# LOGIC.net
KiCad netlist of a schematic drawn in Altium Designer
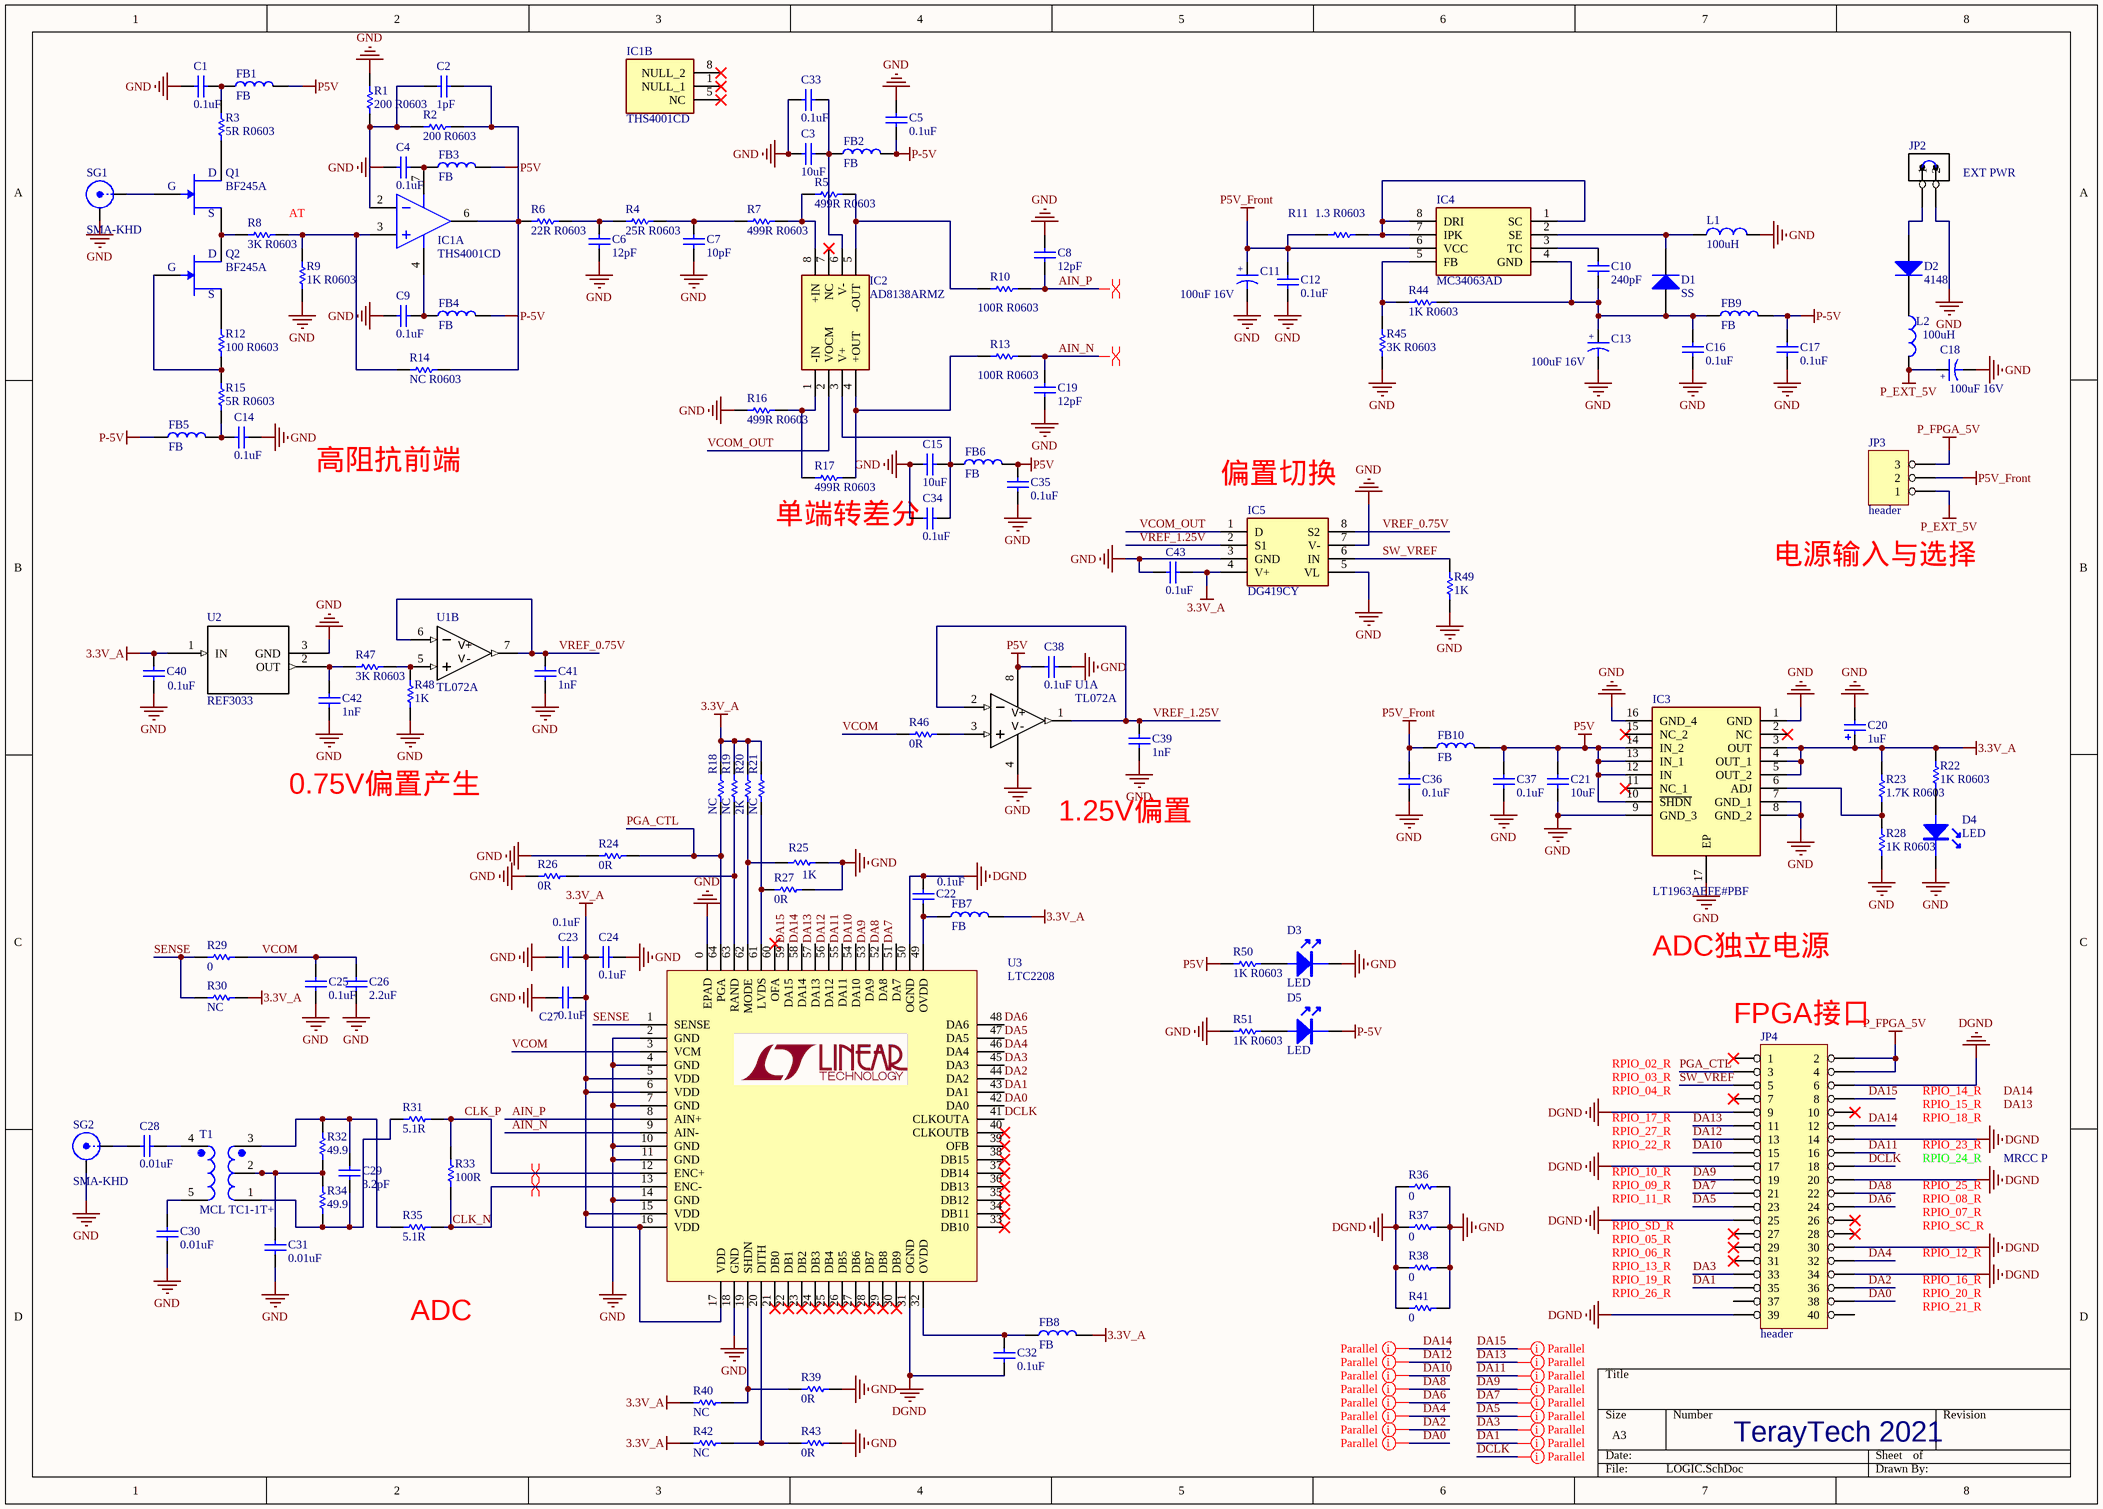
[diagram p0: LOGIC.SchDoc]

(export (version "E")
  (design (tool "Eeschema 10.0.6"))
  (components
    (comp (ref "C1")
      (value "0.1uF")
      (footprint "0603_C")
      (description "Capacitor")
      (fields (field (name "PUBLISHER") "Altium Limited"))
      (libsource (lib "My Footprint") (part "CAP"))
    )
    (comp (ref "C2")
      (value "1pF")
      (footprint "0603_C")
      (description "Capacitor")
      (fields (field (name "PUBLISHER") "Altium Limited"))
      (libsource (lib "My Footprint") (part "CAP"))
    )
    (comp (ref "C3")
      (value "10uF")
      (footprint "0805_c")
      (description "Capacitor")
      (fields (field (name "PUBLISHER") "Altium Limited"))
      (libsource (lib "My Footprint") (part "CAP"))
    )
    (comp (ref "C4")
      (value "0.1uF")
      (footprint "0603_C")
      (description "Capacitor")
      (fields (field (name "PUBLISHER") "Altium Limited"))
      (libsource (lib "My Footprint") (part "CAP"))
    )
    (comp (ref "C5")
      (value "0.1uF")
      (footprint "0603_C")
      (description "Capacitor")
      (fields (field (name "PUBLISHER") "Altium Limited"))
      (libsource (lib "My Footprint") (part "CAP"))
    )
    (comp (ref "C6")
      (value "12pF")
      (footprint "0603_C")
      (description "Capacitor")
      (fields (field (name "PUBLISHER") "Altium Limited"))
      (libsource (lib "My Footprint") (part "CAP"))
    )
    (comp (ref "C7")
      (value "10pF")
      (footprint "0603_C")
      (description "Capacitor")
      (fields (field (name "PUBLISHER") "Altium Limited"))
      (libsource (lib "My Footprint") (part "CAP"))
    )
    (comp (ref "C8")
      (value "12pF")
      (footprint "0603_C")
      (description "Capacitor")
      (fields (field (name "PUBLISHER") "Altium Limited"))
      (libsource (lib "My Footprint") (part "CAP"))
    )
    (comp (ref "C9")
      (value "0.1uF")
      (footprint "0603_C")
      (description "Capacitor")
      (fields (field (name "PUBLISHER") "Altium Limited"))
      (libsource (lib "My Footprint") (part "CAP"))
    )
    (comp (ref "C10")
      (value "240pF")
      (footprint "0603_C")
      (description "Capacitor")
      (fields (field (name "PUBLISHER") "Altium Limited"))
      (libsource (lib "My Footprint") (part "CAP"))
    )
    (comp (ref "C11")
      (value "100uF 16V")
      (footprint "CAP_1000x2000")
      (libsource (lib "My Footprint") (part "CAP1"))
    )
    (comp (ref "C12")
      (value "0.1uF")
      (footprint "0603_C")
      (description "Capacitor")
      (fields (field (name "PUBLISHER") "Altium Limited"))
      (libsource (lib "My Footprint") (part "CAP"))
    )
    (comp (ref "C13")
      (value "100uF 16V")
      (footprint "CAP_1000x2000")
      (libsource (lib "My Footprint") (part "CAP1"))
    )
    (comp (ref "C14")
      (value "0.1uF")
      (footprint "0603_C")
      (description "Capacitor")
      (fields (field (name "PUBLISHER") "Altium Limited"))
      (libsource (lib "My Footprint") (part "CAP"))
    )
    (comp (ref "C15")
      (value "10uF")
      (footprint "0805_c")
      (description "Capacitor")
      (fields (field (name "PUBLISHER") "Altium Limited"))
      (libsource (lib "My Footprint") (part "CAP"))
    )
    (comp (ref "C16")
      (value "0.1uF")
      (footprint "0805_c")
      (description "Capacitor")
      (fields (field (name "PUBLISHER") "Altium Limited"))
      (libsource (lib "My Footprint") (part "CAP"))
    )
    (comp (ref "C17")
      (value "0.1uF")
      (footprint "0805_c")
      (description "Capacitor")
      (fields (field (name "PUBLISHER") "Altium Limited"))
      (libsource (lib "My Footprint") (part "CAP"))
    )
    (comp (ref "C18")
      (value "100uF 16V")
      (footprint "CAP_1000x2000")
      (libsource (lib "My Footprint") (part "CAP1"))
    )
    (comp (ref "C19")
      (value "12pF")
      (footprint "0603_C")
      (description "Capacitor")
      (fields (field (name "PUBLISHER") "Altium Limited"))
      (libsource (lib "My Footprint") (part "CAP"))
    )
    (comp (ref "C20")
      (value "1uF")
      (footprint "CAPC3528B")
      (description "Capacitor")
      (fields (field (name "PUBLISHER") "Altium Limited"))
      (libsource (lib "My Footprint") (part "CAP_tan"))
    )
    (comp (ref "C21")
      (value "10uF")
      (footprint "0805_c")
      (description "Capacitor")
      (fields (field (name "PUBLISHER") "Altium Limited"))
      (libsource (lib "My Footprint") (part "CAP"))
    )
    (comp (ref "C22")
      (value "0.1uF")
      (footprint "0603_C")
      (description "Capacitor")
      (fields (field (name "PUBLISHER") "Altium Limited"))
      (libsource (lib "My Footprint") (part "CAP"))
    )
    (comp (ref "C23")
      (value "0.1uF")
      (footprint "0603_C")
      (description "Capacitor")
      (fields (field (name "PUBLISHER") "Altium Limited"))
      (libsource (lib "My Footprint") (part "CAP"))
    )
    (comp (ref "C24")
      (value "0.1uF")
      (footprint "0603_C")
      (description "Capacitor")
      (fields (field (name "PUBLISHER") "Altium Limited"))
      (libsource (lib "My Footprint") (part "CAP"))
    )
    (comp (ref "C25")
      (value "0.1uF")
      (footprint "0603_C")
      (description "Capacitor")
      (fields (field (name "PUBLISHER") "Altium Limited"))
      (libsource (lib "My Footprint") (part "CAP"))
    )
    (comp (ref "C26")
      (value "2.2uF")
      (footprint "0603_C")
      (description "Capacitor")
      (fields (field (name "PUBLISHER") "Altium Limited"))
      (libsource (lib "My Footprint") (part "CAP"))
    )
    (comp (ref "C27")
      (value "0.1uF")
      (footprint "0603_C")
      (description "Capacitor")
      (fields (field (name "PUBLISHER") "Altium Limited"))
      (libsource (lib "My Footprint") (part "CAP"))
    )
    (comp (ref "C28")
      (value "0.01uF")
      (footprint "0603_C")
      (description "Capacitor")
      (fields (field (name "PUBLISHER") "Altium Limited"))
      (libsource (lib "My Footprint") (part "CAP"))
    )
    (comp (ref "C29")
      (value "8.2pF")
      (footprint "0603_C")
      (description "Capacitor")
      (fields (field (name "PUBLISHER") "Altium Limited"))
      (libsource (lib "My Footprint") (part "CAP"))
    )
    (comp (ref "C30")
      (value "0.01uF")
      (footprint "0603_C")
      (description "Capacitor")
      (fields (field (name "PUBLISHER") "Altium Limited"))
      (libsource (lib "My Footprint") (part "CAP"))
    )
    (comp (ref "C31")
      (value "0.01uF")
      (footprint "0603_C")
      (description "Capacitor")
      (fields (field (name "PUBLISHER") "Altium Limited"))
      (libsource (lib "My Footprint") (part "CAP"))
    )
    (comp (ref "C32")
      (value "0.1uF")
      (footprint "0603_C")
      (description "Capacitor")
      (fields (field (name "PUBLISHER") "Altium Limited"))
      (libsource (lib "My Footprint") (part "CAP"))
    )
    (comp (ref "C33")
      (value "0.1uF")
      (footprint "0603_C")
      (description "Capacitor")
      (fields (field (name "PUBLISHER") "Altium Limited"))
      (libsource (lib "My Footprint") (part "CAP"))
    )
    (comp (ref "C34")
      (value "0.1uF")
      (footprint "0603_C")
      (description "Capacitor")
      (fields (field (name "PUBLISHER") "Altium Limited"))
      (libsource (lib "My Footprint") (part "CAP"))
    )
    (comp (ref "C35")
      (value "0.1uF")
      (footprint "0603_C")
      (description "Capacitor")
      (fields (field (name "PUBLISHER") "Altium Limited"))
      (libsource (lib "My Footprint") (part "CAP"))
    )
    (comp (ref "C36")
      (value "0.1uF")
      (footprint "0805_c")
      (description "Capacitor")
      (fields (field (name "PUBLISHER") "Altium Limited"))
      (libsource (lib "My Footprint") (part "CAP"))
    )
    (comp (ref "C37")
      (value "0.1uF")
      (footprint "0805_c")
      (description "Capacitor")
      (fields (field (name "PUBLISHER") "Altium Limited"))
      (libsource (lib "My Footprint") (part "CAP"))
    )
    (comp (ref "C38")
      (value "0.1uF")
      (footprint "0603_C")
      (description "Capacitor")
      (fields (field (name "PUBLISHER") "Altium Limited"))
      (libsource (lib "My Footprint") (part "CAP"))
    )
    (comp (ref "C39")
      (value "1nF")
      (footprint "0603_C")
      (description "Capacitor")
      (fields (field (name "PUBLISHER") "Altium Limited"))
      (libsource (lib "My Footprint") (part "CAP"))
    )
    (comp (ref "C40")
      (value "0.1uF")
      (footprint "0603_C")
      (description "Capacitor")
      (fields (field (name "PUBLISHER") "Altium Limited"))
      (libsource (lib "My Footprint") (part "CAP"))
    )
    (comp (ref "C41")
      (value "1nF")
      (footprint "0603_C")
      (description "Capacitor")
      (fields (field (name "PUBLISHER") "Altium Limited"))
      (libsource (lib "My Footprint") (part "CAP"))
    )
    (comp (ref "C42")
      (value "1nF")
      (footprint "0603_C")
      (description "Capacitor")
      (fields (field (name "PUBLISHER") "Altium Limited"))
      (libsource (lib "My Footprint") (part "CAP"))
    )
    (comp (ref "C43")
      (value "0.1uF")
      (footprint "0603_C")
      (description "Capacitor")
      (fields (field (name "PUBLISHER") "Altium Limited"))
      (libsource (lib "My Footprint") (part "CAP"))
    )
    (comp (ref "D1") (value "SS") (footprint "DO-214AC(") (libsource (lib "My Footprint") (part "SS24")))
    (comp (ref "D2")
      (value "4148")
      (footprint "DO-214AC(")
      (description "High Conductance Fast Diode")
      (fields (field (name "PUBLISHER") "Altium Limited"))
      (libsource (lib "My Footprint") (part "1N4148"))
    )
    (comp (ref "D3")
      (value "LED")
      (footprint "0603_LED")
      (description "LED 发光二极管")
      (libsource (lib "My Footprint") (part "LED"))
    )
    (comp (ref "D4")
      (value "LED")
      (footprint "0603_LED")
      (description "LED 发光二极管")
      (libsource (lib "My Footprint") (part "LED"))
    )
    (comp (ref "D5")
      (value "LED")
      (footprint "0603_LED")
      (description "LED 发光二极管")
      (libsource (lib "My Footprint") (part "LED"))
    )
    (comp (ref "FB1")
      (value "FB")
      (footprint "FB0603")
      (description "磁珠")
      (libsource (lib "My Footprint") (part "FB"))
    )
    (comp (ref "FB2")
      (value "FB")
      (footprint "FB0603")
      (description "磁珠")
      (libsource (lib "My Footprint") (part "FB"))
    )
    (comp (ref "FB3")
      (value "FB")
      (footprint "FB0603")
      (description "磁珠")
      (libsource (lib "My Footprint") (part "FB"))
    )
    (comp (ref "FB4")
      (value "FB")
      (footprint "FB0603")
      (description "磁珠")
      (libsource (lib "My Footprint") (part "FB"))
    )
    (comp (ref "FB5")
      (value "FB")
      (footprint "FB0603")
      (description "磁珠")
      (libsource (lib "My Footprint") (part "FB"))
    )
    (comp (ref "FB6")
      (value "FB")
      (footprint "FB0603")
      (description "磁珠")
      (libsource (lib "My Footprint") (part "FB"))
    )
    (comp (ref "FB7")
      (value "FB")
      (footprint "FB0603")
      (description "磁珠")
      (libsource (lib "My Footprint") (part "FB"))
    )
    (comp (ref "FB8")
      (value "FB")
      (footprint "0603")
      (description "磁珠")
      (libsource (lib "My Footprint") (part "FB"))
    )
    (comp (ref "FB9")
      (value "FB")
      (footprint "0805")
      (description "磁珠")
      (libsource (lib "My Footprint") (part "FB"))
    )
    (comp (ref "FB10")
      (value "FB")
      (footprint "0805")
      (description "磁珠")
      (libsource (lib "My Footprint") (part "FB"))
    )
    (comp (ref "IC1")
      (value "THS4001CD")
      (footprint "SamacSys:SOIC127P600X175-8N")
      (description "Integrated Circuit")
      (fields (field (name "MOUSER PART NUMBER") "595-THS4001CD"))
      (libsource (lib "SamacSys") (part "THS4001CD"))
    )
    (comp (ref "IC2")
      (value "AD8138ARMZ")
      (footprint "SamacSys:SOP65P490X110-8N")
      (description "Integrated Circuit")
      (fields (field (name "MOUSER PART NUMBER") "584-AD8138ARMZ"))
      (libsource (lib "SamacSys") (part "AD8138ARMZ"))
    )
    (comp (ref "IC3")
      (value "LT1963AEFE#PBF")
      (footprint "SOP65P640X110-17N")
      (description "Integrated Circuit")
      (fields (field (name "MOUSER PART NUMBER") "584-LT1963AEFE#PBF"))
      (libsource (lib "SamacSys") (part "LT1963AEFE#PBF"))
    )
    (comp (ref "IC4")
      (value "MC34063AD")
      (footprint "SamacSys:SOIC127P600X175-8N")
      (description "Integrated Circuit")
      (fields (field (name "MOUSER PART NUMBER") "595-MC34063AD"))
      (libsource (lib "SamacSys") (part "MC34063AD"))
    )
    (comp (ref "IC5")
      (value "DG419CY")
      (footprint "SOIC-8")
      (description "Integrated Circuit")
      (libsource (lib "SamacSys") (part "DG419CY"))
    )
    (comp (ref "JP2")
      (value "EXT PWR")
      (footprint "CCM-5.08-2P")
      (libsource (lib "My Footprint") (part "HEADER 2"))
    )
    (comp (ref "JP3")
      (value "header")
      (footprint "header3")
      (libsource (lib "My Footprint") (part "HEADER 3"))
    )
    (comp (ref "JP4")
      (value "header")
      (footprint "header2X20")
      (libsource (lib "My Footprint") (part "HEADER 20X2"))
    )
    (comp (ref "L1") (value "100uH") (footprint "L 5x5") (libsource (lib "My Footprint") (part "Inductor")))
    (comp (ref "L2") (value "100uH") (footprint "1206") (libsource (lib "My Footprint") (part "Inductor")))
    (comp (ref "Q1")
      (value "BF245A")
      (footprint "SamacSys:TO127P419X482X1041-3P")
      (description "Transistor")
      (fields (field (name "MOUSER PART NUMBER") "863-BF245A"))
      (libsource (lib "SamacSys") (part "BF245A"))
    )
    (comp (ref "Q2")
      (value "BF245A")
      (footprint "SamacSys:TO127P419X482X1041-3P")
      (description "Transistor")
      (fields (field (name "MOUSER PART NUMBER") "863-BF245A"))
      (libsource (lib "SamacSys") (part "BF245A"))
    )
    (comp (ref "R1")
      (value "200 R0603")
      (footprint "0603_R")
      (description "Resistor")
      (fields (field (name "PUBLISHER") "Altium Limited"))
      (libsource (lib "My Footprint") (part "RES"))
    )
    (comp (ref "R2")
      (value "200 R0603")
      (footprint "0603_R")
      (description "Resistor")
      (fields (field (name "PUBLISHER") "Altium Limited"))
      (libsource (lib "My Footprint") (part "RES"))
    )
    (comp (ref "R3")
      (value "5R R0603")
      (footprint "0603_R")
      (description "Resistor")
      (fields (field (name "PUBLISHER") "Altium Limited"))
      (libsource (lib "My Footprint") (part "RES"))
    )
    (comp (ref "R4")
      (value "25R R0603")
      (footprint "0603_R")
      (description "Resistor")
      (fields (field (name "PUBLISHER") "Altium Limited"))
      (libsource (lib "My Footprint") (part "RES"))
    )
    (comp (ref "R5")
      (value "499R R0603")
      (footprint "0603_R")
      (description "Resistor")
      (fields (field (name "PUBLISHER") "Altium Limited"))
      (libsource (lib "My Footprint") (part "RES"))
    )
    (comp (ref "R6")
      (value "22R R0603")
      (footprint "0603_R")
      (description "Resistor")
      (fields (field (name "PUBLISHER") "Altium Limited"))
      (libsource (lib "My Footprint") (part "RES"))
    )
    (comp (ref "R7")
      (value "499R R0603")
      (footprint "0603_R")
      (description "Resistor")
      (fields (field (name "PUBLISHER") "Altium Limited"))
      (libsource (lib "My Footprint") (part "RES"))
    )
    (comp (ref "R8")
      (value "3K R0603")
      (footprint "0603_R")
      (description "Resistor")
      (fields (field (name "PUBLISHER") "Altium Limited"))
      (libsource (lib "My Footprint") (part "RES"))
    )
    (comp (ref "R9")
      (value "1K R0603")
      (footprint "0603_R")
      (description "Resistor")
      (fields (field (name "PUBLISHER") "Altium Limited"))
      (libsource (lib "My Footprint") (part "RES"))
    )
    (comp (ref "R10")
      (value "100R R0603")
      (footprint "0603_R")
      (description "Resistor")
      (fields (field (name "PUBLISHER") "Altium Limited"))
      (libsource (lib "My Footprint") (part "RES"))
    )
    (comp (ref "R11")
      (value "1.3 R0603")
      (footprint "0603_R")
      (description "Resistor")
      (fields (field (name "PUBLISHER") "Altium Limited"))
      (libsource (lib "My Footprint") (part "RES"))
    )
    (comp (ref "R12")
      (value "100 R0603")
      (footprint "0603_R")
      (description "Resistor")
      (fields (field (name "PUBLISHER") "Altium Limited"))
      (libsource (lib "My Footprint") (part "RES"))
    )
    (comp (ref "R13")
      (value "100R R0603")
      (footprint "0603_R")
      (description "Resistor")
      (fields (field (name "PUBLISHER") "Altium Limited"))
      (libsource (lib "My Footprint") (part "RES"))
    )
    (comp (ref "R14")
      (value "NC R0603")
      (footprint "0603_R")
      (description "Resistor")
      (fields (field (name "PUBLISHER") "Altium Limited"))
      (libsource (lib "My Footprint") (part "RES"))
    )
    (comp (ref "R15")
      (value "5R R0603")
      (footprint "0603_R")
      (description "Resistor")
      (fields (field (name "PUBLISHER") "Altium Limited"))
      (libsource (lib "My Footprint") (part "RES"))
    )
    (comp (ref "R16")
      (value "499R R0603")
      (footprint "0603_R")
      (description "Resistor")
      (fields (field (name "PUBLISHER") "Altium Limited"))
      (libsource (lib "My Footprint") (part "RES"))
    )
    (comp (ref "R17")
      (value "499R R0603")
      (footprint "0603_R")
      (description "Resistor")
      (fields (field (name "PUBLISHER") "Altium Limited"))
      (libsource (lib "My Footprint") (part "RES"))
    )
    (comp (ref "R18")
      (value "NC")
      (footprint "0603_R")
      (description "Resistor")
      (fields (field (name "PUBLISHER") "Altium Limited"))
      (libsource (lib "My Footprint") (part "RES0"))
    )
    (comp (ref "R19")
      (value "NC")
      (footprint "0603_R")
      (description "Resistor")
      (fields (field (name "PUBLISHER") "Altium Limited"))
      (libsource (lib "My Footprint") (part "RES0"))
    )
    (comp (ref "R20")
      (value "2K")
      (footprint "0603_R")
      (description "Resistor")
      (fields (field (name "PUBLISHER") "Altium Limited"))
      (libsource (lib "My Footprint") (part "RES0"))
    )
    (comp (ref "R21")
      (value "NC")
      (footprint "0603_R")
      (description "Resistor")
      (fields (field (name "PUBLISHER") "Altium Limited"))
      (libsource (lib "My Footprint") (part "RES0"))
    )
    (comp (ref "R22")
      (value "1K R0603")
      (footprint "0603_R")
      (description "Resistor")
      (fields (field (name "PUBLISHER") "Altium Limited"))
      (libsource (lib "My Footprint") (part "RES"))
    )
    (comp (ref "R23")
      (value "1.7K R0603")
      (footprint "0603_R")
      (description "Resistor")
      (fields (field (name "PUBLISHER") "Altium Limited"))
      (libsource (lib "My Footprint") (part "RES"))
    )
    (comp (ref "R24")
      (value "0R")
      (footprint "0603_R")
      (description "Resistor")
      (fields (field (name "PUBLISHER") "Altium Limited"))
      (libsource (lib "My Footprint") (part "RES0"))
    )
    (comp (ref "R25")
      (value "1K")
      (footprint "0603_R")
      (description "Resistor")
      (fields (field (name "PUBLISHER") "Altium Limited"))
      (libsource (lib "My Footprint") (part "RES0"))
    )
    (comp (ref "R26")
      (value "0R")
      (footprint "0603_R")
      (description "Resistor")
      (fields (field (name "PUBLISHER") "Altium Limited"))
      (libsource (lib "My Footprint") (part "RES0"))
    )
    (comp (ref "R27")
      (value "0R")
      (footprint "0603_R")
      (description "Resistor")
      (fields (field (name "PUBLISHER") "Altium Limited"))
      (libsource (lib "My Footprint") (part "RES0"))
    )
    (comp (ref "R28")
      (value "1K R0603")
      (footprint "0603_R")
      (description "Resistor")
      (fields (field (name "PUBLISHER") "Altium Limited"))
      (libsource (lib "My Footprint") (part "RES"))
    )
    (comp (ref "R29")
      (value "0")
      (footprint "0603_R")
      (description "Resistor")
      (fields (field (name "PUBLISHER") "Altium Limited"))
      (libsource (lib "My Footprint") (part "RES0"))
    )
    (comp (ref "R30")
      (value "NC")
      (footprint "0603_R")
      (description "Resistor")
      (fields (field (name "PUBLISHER") "Altium Limited"))
      (libsource (lib "My Footprint") (part "RES0"))
    )
    (comp (ref "R31")
      (value "5.1R")
      (footprint "0603_R")
      (description "Resistor")
      (fields (field (name "PUBLISHER") "Altium Limited"))
      (libsource (lib "My Footprint") (part "RES0"))
    )
    (comp (ref "R32")
      (value "49.9")
      (footprint "0603_R")
      (description "Resistor")
      (fields (field (name "PUBLISHER") "Altium Limited"))
      (libsource (lib "My Footprint") (part "RES0"))
    )
    (comp (ref "R33")
      (value "100R")
      (footprint "0603_R")
      (description "Resistor")
      (fields (field (name "PUBLISHER") "Altium Limited"))
      (libsource (lib "My Footprint") (part "RES0"))
    )
    (comp (ref "R34")
      (value "49.9")
      (footprint "0603_R")
      (description "Resistor")
      (fields (field (name "PUBLISHER") "Altium Limited"))
      (libsource (lib "My Footprint") (part "RES0"))
    )
    (comp (ref "R35")
      (value "5.1R")
      (footprint "0603_R")
      (description "Resistor")
      (fields (field (name "PUBLISHER") "Altium Limited"))
      (libsource (lib "My Footprint") (part "RES0"))
    )
    (comp (ref "R36")
      (value "0")
      (footprint "0603_R")
      (description "Resistor")
      (fields (field (name "PUBLISHER") "Altium Limited"))
      (libsource (lib "My Footprint") (part "RES0"))
    )
    (comp (ref "R37")
      (value "0")
      (footprint "0603_R")
      (description "Resistor")
      (fields (field (name "PUBLISHER") "Altium Limited"))
      (libsource (lib "My Footprint") (part "RES0"))
    )
    (comp (ref "R38")
      (value "0")
      (footprint "0603_R")
      (description "Resistor")
      (fields (field (name "PUBLISHER") "Altium Limited"))
      (libsource (lib "My Footprint") (part "RES0"))
    )
    (comp (ref "R39")
      (value "0R")
      (footprint "0603_R")
      (description "Resistor")
      (fields (field (name "PUBLISHER") "Altium Limited"))
      (libsource (lib "My Footprint") (part "RES0"))
    )
    (comp (ref "R40")
      (value "NC")
      (footprint "0603_R")
      (description "Resistor")
      (fields (field (name "PUBLISHER") "Altium Limited"))
      (libsource (lib "My Footprint") (part "RES0"))
    )
    (comp (ref "R41")
      (value "0")
      (footprint "0603_R")
      (description "Resistor")
      (fields (field (name "PUBLISHER") "Altium Limited"))
      (libsource (lib "My Footprint") (part "RES0"))
    )
    (comp (ref "R42")
      (value "NC")
      (footprint "0603_R")
      (description "Resistor")
      (fields (field (name "PUBLISHER") "Altium Limited"))
      (libsource (lib "My Footprint") (part "RES0"))
    )
    (comp (ref "R43")
      (value "0R")
      (footprint "0603_R")
      (description "Resistor")
      (fields (field (name "PUBLISHER") "Altium Limited"))
      (libsource (lib "My Footprint") (part "RES0"))
    )
    (comp (ref "R44")
      (value "1K R0603")
      (footprint "0603_R")
      (description "Resistor")
      (fields (field (name "PUBLISHER") "Altium Limited"))
      (libsource (lib "My Footprint") (part "RES"))
    )
    (comp (ref "R45")
      (value "3K R0603")
      (footprint "0603_R")
      (description "Resistor")
      (fields (field (name "PUBLISHER") "Altium Limited"))
      (libsource (lib "My Footprint") (part "RES"))
    )
    (comp (ref "R46")
      (value "0R")
      (footprint "0603_R")
      (description "Resistor")
      (fields (field (name "PUBLISHER") "Altium Limited"))
      (libsource (lib "My Footprint") (part "RES0"))
    )
    (comp (ref "R47")
      (value "3K R0603")
      (footprint "0603_R")
      (description "Resistor")
      (fields (field (name "PUBLISHER") "Altium Limited"))
      (libsource (lib "My Footprint") (part "RES"))
    )
    (comp (ref "R48")
      (value "1K")
      (footprint "0603_R")
      (description "Resistor")
      (fields (field (name "PUBLISHER") "Altium Limited"))
      (libsource (lib "My Footprint") (part "RES0"))
    )
    (comp (ref "R49")
      (value "1K")
      (footprint "0603_R")
      (description "Resistor")
      (fields (field (name "PUBLISHER") "Altium Limited"))
      (libsource (lib "My Footprint") (part "RES0"))
    )
    (comp (ref "R50")
      (value "1K R0603")
      (footprint "0603_R")
      (description "Resistor")
      (fields (field (name "PUBLISHER") "Altium Limited"))
      (libsource (lib "My Footprint") (part "RES"))
    )
    (comp (ref "R51")
      (value "1K R0603")
      (footprint "0603_R")
      (description "Resistor")
      (fields (field (name "PUBLISHER") "Altium Limited"))
      (libsource (lib "My Footprint") (part "RES"))
    )
    (comp (ref "SG1") (value "SMA-KHD") (footprint "SMA-2") (libsource (lib "") (part "SMA_KHD_1")))
    (comp (ref "SG2")
      (value "SMA-KHD")
      (footprint "SMA-H - duplicate")
      (libsource (lib "My Footprint") (part "SMA_KHD"))
    )
    (comp (ref "T1")
      (value "MCL TC1-1T+")
      (footprint "TC1-1T")
      (libsource (lib "My Footprint") (part "TC1-1T+"))
    )
    (comp (ref "U1")
      (value "TL072A")
      (footprint "SOIC-8")
      (description "Imported")
      (fields
        (field (name "MANUFACTURER") "Texas Instruments")
        (field (name "GENERIC_PART_NUMBER") "OPA2365")
      )
      (libsource (lib "My Footprint") (part "OPA2365"))
    )
    (comp (ref "U2")
      (value "REF3033")
      (footprint "DBZ3")
      (description "Imported")
      (fields
        (field (name "MANUFACTURER") "Texas Instruments")
        (field (name "MANUFACTURER_PART_NUMBER") "ref3033_dbz_3")
      )
      (libsource (lib "My Footprint") (part "REF3033_DBZ_3"))
    )
    (comp (ref "U3") (value "LTC2208") (footprint "QFN64") (libsource (lib "My Footprint") (part "LTC2208")))
  )
  (nets
    (net (code "1") (name "/AIN_N") (class "Default")
      (node (ref "C19") (pin "2") (pinfunction "2_2") (pintype "passive"))
      (node (ref "R13") (pin "2") (pinfunction "2_2") (pintype "passive"))
      (node (ref "U3") (pin "9") (pinfunction "AIN-_9") (pintype "passive"))
    )
    (net (code "2") (name "/AIN_P") (class "Default")
      (node (ref "C8") (pin "1") (pinfunction "1_1") (pintype "passive"))
      (node (ref "R10") (pin "2") (pinfunction "2_2") (pintype "passive"))
      (node (ref "U3") (pin "8") (pinfunction "AIN+_8") (pintype "passive"))
    )
    (net (code "3") (name "/CLK_N") (class "Default")
      (node (ref "R33") (pin "2") (pinfunction "2_2") (pintype "passive"))
      (node (ref "R35") (pin "2") (pinfunction "2_2") (pintype "passive"))
      (node (ref "U3") (pin "13") (pinfunction "ENC-_13") (pintype "passive"))
    )
    (net (code "4") (name "/CLK_P") (class "Default")
      (node (ref "R31") (pin "2") (pinfunction "2_2") (pintype "passive"))
      (node (ref "R33") (pin "1") (pinfunction "1_1") (pintype "passive"))
      (node (ref "U3") (pin "12") (pinfunction "ENC+_12") (pintype "passive"))
    )
    (net (code "5") (name "/DA0") (class "Default")
      (node (ref "JP4") (pin "38") (pinfunction "38_38") (pintype "passive"))
      (node (ref "U3") (pin "42") (pinfunction "DA0_42") (pintype "passive"))
    )
    (net (code "6") (name "/DA1") (class "Default")
      (node (ref "JP4") (pin "35") (pinfunction "35_35") (pintype "passive"))
      (node (ref "U3") (pin "43") (pinfunction "DA1_43") (pintype "passive"))
    )
    (net (code "7") (name "/DA2") (class "Default")
      (node (ref "JP4") (pin "36") (pinfunction "36_36") (pintype "passive"))
      (node (ref "U3") (pin "44") (pinfunction "DA2_44") (pintype "passive"))
    )
    (net (code "8") (name "/DA3") (class "Default")
      (node (ref "JP4") (pin "33") (pinfunction "33_33") (pintype "passive"))
      (node (ref "U3") (pin "45") (pinfunction "DA3_45") (pintype "passive"))
    )
    (net (code "9") (name "/DA4") (class "Default")
      (node (ref "JP4") (pin "32") (pinfunction "32_32") (pintype "passive"))
      (node (ref "U3") (pin "46") (pinfunction "DA4_46") (pintype "passive"))
    )
    (net (code "10") (name "/DA5") (class "Default")
      (node (ref "JP4") (pin "23") (pinfunction "23_23") (pintype "passive"))
      (node (ref "U3") (pin "47") (pinfunction "DA5_47") (pintype "passive"))
    )
    (net (code "11") (name "/DA6") (class "Default")
      (node (ref "JP4") (pin "24") (pinfunction "24_24") (pintype "passive"))
      (node (ref "U3") (pin "48") (pinfunction "DA6_48") (pintype "passive"))
    )
    (net (code "12") (name "/DA7") (class "Default")
      (node (ref "JP4") (pin "21") (pinfunction "21_21") (pintype "passive"))
      (node (ref "U3") (pin "51") (pinfunction "DA7_51") (pintype "passive"))
    )
    (net (code "13") (name "/DA8") (class "Default")
      (node (ref "JP4") (pin "22") (pinfunction "22_22") (pintype "passive"))
      (node (ref "U3") (pin "52") (pinfunction "DA8_52") (pintype "passive"))
    )
    (net (code "14") (name "/DA9") (class "Default")
      (node (ref "JP4") (pin "19") (pinfunction "19_19") (pintype "passive"))
      (node (ref "U3") (pin "53") (pinfunction "DA9_53") (pintype "passive"))
    )
    (net (code "15") (name "/DA10") (class "Default")
      (node (ref "JP4") (pin "15") (pinfunction "15_15") (pintype "passive"))
      (node (ref "U3") (pin "54") (pinfunction "DA10_54") (pintype "passive"))
    )
    (net (code "16") (name "/DA11") (class "Default")
      (node (ref "JP4") (pin "16") (pinfunction "16_16") (pintype "passive"))
      (node (ref "U3") (pin "55") (pinfunction "DA11_55") (pintype "passive"))
    )
    (net (code "17") (name "/DA12") (class "Default")
      (node (ref "JP4") (pin "13") (pinfunction "13_13") (pintype "passive"))
      (node (ref "U3") (pin "56") (pinfunction "DA12_56") (pintype "passive"))
    )
    (net (code "18") (name "/DA13") (class "Default")
      (node (ref "JP4") (pin "11") (pinfunction "11_11") (pintype "passive"))
      (node (ref "U3") (pin "57") (pinfunction "DA13_57") (pintype "passive"))
    )
    (net (code "19") (name "/DA14") (class "Default")
      (node (ref "JP4") (pin "12") (pinfunction "12_12") (pintype "passive"))
      (node (ref "U3") (pin "58") (pinfunction "DA14_58") (pintype "passive"))
    )
    (net (code "20") (name "/DA15") (class "Default")
      (node (ref "JP4") (pin "8") (pinfunction "8_8") (pintype "passive"))
      (node (ref "U3") (pin "59") (pinfunction "DA15_59") (pintype "passive"))
    )
    (net (code "21") (name "/DCLK") (class "Default")
      (node (ref "JP4") (pin "18") (pinfunction "18_18") (pintype "passive"))
      (node (ref "U3") (pin "41") (pinfunction "CLKOUTA_41") (pintype "passive"))
    )
    (net (code "22") (name "/PGA_CTL") (class "Default")
      (node (ref "JP4") (pin "3") (pinfunction "3_3") (pintype "passive"))
      (node (ref "R18") (pin "2") (pinfunction "2_2") (pintype "passive"))
      (node (ref "R24") (pin "1") (pinfunction "1_1") (pintype "passive"))
      (node (ref "U3") (pin "64") (pinfunction "PGA_64") (pintype "passive"))
    )
    (net (code "23") (name "/SENSE") (class "Default")
      (node (ref "R29") (pin "2") (pinfunction "2_2") (pintype "passive"))
      (node (ref "R30") (pin "2") (pinfunction "2_2") (pintype "passive"))
      (node (ref "U3") (pin "1") (pinfunction "SENSE_1") (pintype "passive"))
    )
    (net (code "24") (name "/SW_VREF") (class "Default")
      (node (ref "IC5") (pin "6") (pinfunction "IN_6") (pintype "passive"))
      (node (ref "JP4") (pin "5") (pinfunction "5_5") (pintype "passive"))
      (node (ref "R49") (pin "1") (pinfunction "1_1") (pintype "passive"))
    )
    (net (code "25") (name "/VCOM") (class "Default")
      (node (ref "C25") (pin "2") (pinfunction "2_2") (pintype "passive"))
      (node (ref "C26") (pin "2") (pinfunction "2_2") (pintype "passive"))
      (node (ref "R29") (pin "1") (pinfunction "1_1") (pintype "passive"))
      (node (ref "R46") (pin "2") (pinfunction "2_2") (pintype "passive"))
      (node (ref "U3") (pin "3") (pinfunction "VCM_3") (pintype "passive"))
    )
    (net (code "26") (name "/VCOM_OUT") (class "Default")
      (node (ref "IC2") (pin "2") (pinfunction "VOCM_2") (pintype "passive"))
      (node (ref "IC5") (pin "1") (pinfunction "D_1") (pintype "passive"))
    )
    (net (code "27") (name "/VREF_0.75V") (class "Default")
      (node (ref "C41") (pin "2") (pinfunction "2_2") (pintype "passive"))
      (node (ref "IC5") (pin "8") (pinfunction "S2_8") (pintype "passive"))
      (node (ref "U1") (pin "6") (pinfunction "2IN-_6") (pintype "input"))
      (node (ref "U1") (pin "7") (pinfunction "2OUT_7") (pintype "output"))
    )
    (net (code "28") (name "/VREF_1.25V") (class "Default")
      (node (ref "C39") (pin "2") (pinfunction "2_2") (pintype "passive"))
      (node (ref "IC5") (pin "2") (pinfunction "S1_2") (pintype "passive"))
      (node (ref "U1") (pin "1") (pinfunction "1OUT_1") (pintype "output"))
      (node (ref "U1") (pin "2") (pinfunction "1IN-_2") (pintype "input"))
    )
    (net (code "29") (name "3.3V_A") (class "Default")
      (node (ref "C20") (pin "1") (pinfunction "1_1") (pintype "passive"))
      (node (ref "C23") (pin "1") (pinfunction "1_1") (pintype "passive"))
      (node (ref "C24") (pin "1") (pinfunction "1_1") (pintype "passive"))
      (node (ref "C27") (pin "1") (pinfunction "1_1") (pintype "passive"))
      (node (ref "C40") (pin "2") (pinfunction "2_2") (pintype "passive"))
      (node (ref "C43") (pin "2") (pinfunction "2_2") (pintype "passive"))
      (node (ref "FB7") (pin "2") (pinfunction "2_2") (pintype "passive"))
      (node (ref "FB8") (pin "2") (pinfunction "2_2") (pintype "passive"))
      (node (ref "IC3") (pin "3") (pinfunction "OUT_3") (pintype "passive"))
      (node (ref "IC3") (pin "4") (pinfunction "OUT_1_4") (pintype "passive"))
      (node (ref "IC3") (pin "5") (pinfunction "OUT_2_5") (pintype "passive"))
      (node (ref "IC5") (pin "4") (pinfunction "V+_4") (pintype "passive"))
      (node (ref "R18") (pin "1") (pinfunction "1_1") (pintype "passive"))
      (node (ref "R19") (pin "1") (pinfunction "1_1") (pintype "passive"))
      (node (ref "R20") (pin "1") (pinfunction "1_1") (pintype "passive"))
      (node (ref "R21") (pin "1") (pinfunction "1_1") (pintype "passive"))
      (node (ref "R22") (pin "2") (pinfunction "2_2") (pintype "passive"))
      (node (ref "R23") (pin "2") (pinfunction "2_2") (pintype "passive"))
      (node (ref "R30") (pin "1") (pinfunction "1_1") (pintype "passive"))
      (node (ref "R40") (pin "2") (pinfunction "2_2") (pintype "passive"))
      (node (ref "R42") (pin "2") (pinfunction "2_2") (pintype "passive"))
      (node (ref "U2") (pin "1") (pinfunction "IN_1") (pintype "input"))
      (node (ref "U3") (pin "15") (pinfunction "VDD_15") (pintype "passive"))
      (node (ref "U3") (pin "16") (pinfunction "VDD_16") (pintype "passive"))
      (node (ref "U3") (pin "17") (pinfunction "VDD_17") (pintype "passive"))
      (node (ref "U3") (pin "5") (pinfunction "VDD_5") (pintype "passive"))
      (node (ref "U3") (pin "6") (pinfunction "VDD_6") (pintype "passive"))
    )
    (net (code "30") (name "DGND") (class "Default")
      (node (ref "C22") (pin "2") (pinfunction "2_2") (pintype "passive"))
      (node (ref "C32") (pin "1") (pinfunction "1_1") (pintype "passive"))
      (node (ref "JP4") (pin "14") (pinfunction "14_14") (pintype "passive"))
      (node (ref "JP4") (pin "17") (pinfunction "17_17") (pintype "passive"))
      (node (ref "JP4") (pin "20") (pinfunction "20_20") (pintype "passive"))
      (node (ref "JP4") (pin "25") (pinfunction "25_25") (pintype "passive"))
      (node (ref "JP4") (pin "30") (pinfunction "30_30") (pintype "passive"))
      (node (ref "JP4") (pin "34") (pinfunction "34_34") (pintype "passive"))
      (node (ref "JP4") (pin "39") (pinfunction "39_39") (pintype "passive"))
      (node (ref "JP4") (pin "6") (pinfunction "6_6") (pintype "passive"))
      (node (ref "JP4") (pin "9") (pinfunction "9_9") (pintype "passive"))
      (node (ref "R36") (pin "2") (pinfunction "2_2") (pintype "passive"))
      (node (ref "R37") (pin "2") (pinfunction "2_2") (pintype "passive"))
      (node (ref "R38") (pin "2") (pinfunction "2_2") (pintype "passive"))
      (node (ref "R41") (pin "2") (pinfunction "2_2") (pintype "passive"))
      (node (ref "U3") (pin "31") (pinfunction "OGND_31") (pintype "passive"))
      (node (ref "U3") (pin "50") (pinfunction "OGND_50") (pintype "passive"))
    )
    (net (code "31") (name "GND") (class "Default")
      (node (ref "C1") (pin "2") (pinfunction "2_2") (pintype "passive"))
      (node (ref "C11") (pin "2") (pinfunction "2_2") (pintype "passive"))
      (node (ref "C12") (pin "1") (pinfunction "1_1") (pintype "passive"))
      (node (ref "C13") (pin "2") (pinfunction "2_2") (pintype "passive"))
      (node (ref "C14") (pin "2") (pinfunction "2_2") (pintype "passive"))
      (node (ref "C15") (pin "2") (pinfunction "2_2") (pintype "passive"))
      (node (ref "C16") (pin "1") (pinfunction "1_1") (pintype "passive"))
      (node (ref "C17") (pin "1") (pinfunction "1_1") (pintype "passive"))
      (node (ref "C18") (pin "2") (pinfunction "2_2") (pintype "passive"))
      (node (ref "C19") (pin "1") (pinfunction "1_1") (pintype "passive"))
      (node (ref "C20") (pin "2") (pinfunction "2_2") (pintype "passive"))
      (node (ref "C21") (pin "1") (pinfunction "1_1") (pintype "passive"))
      (node (ref "C23") (pin "2") (pinfunction "2_2") (pintype "passive"))
      (node (ref "C24") (pin "2") (pinfunction "2_2") (pintype "passive"))
      (node (ref "C25") (pin "1") (pinfunction "1_1") (pintype "passive"))
      (node (ref "C26") (pin "1") (pinfunction "1_1") (pintype "passive"))
      (node (ref "C27") (pin "2") (pinfunction "2_2") (pintype "passive"))
      (node (ref "C3") (pin "2") (pinfunction "2_2") (pintype "passive"))
      (node (ref "C30") (pin "1") (pinfunction "1_1") (pintype "passive"))
      (node (ref "C31") (pin "1") (pinfunction "1_1") (pintype "passive"))
      (node (ref "C33") (pin "2") (pinfunction "2_2") (pintype "passive"))
      (node (ref "C34") (pin "2") (pinfunction "2_2") (pintype "passive"))
      (node (ref "C35") (pin "2") (pinfunction "2_2") (pintype "passive"))
      (node (ref "C36") (pin "1") (pinfunction "1_1") (pintype "passive"))
      (node (ref "C37") (pin "1") (pinfunction "1_1") (pintype "passive"))
      (node (ref "C38") (pin "1") (pinfunction "1_1") (pintype "passive"))
      (node (ref "C39") (pin "1") (pinfunction "1_1") (pintype "passive"))
      (node (ref "C4") (pin "2") (pinfunction "2_2") (pintype "passive"))
      (node (ref "C40") (pin "1") (pinfunction "1_1") (pintype "passive"))
      (node (ref "C41") (pin "1") (pinfunction "1_1") (pintype "passive"))
      (node (ref "C42") (pin "1") (pinfunction "1_1") (pintype "passive"))
      (node (ref "C43") (pin "1") (pinfunction "1_1") (pintype "passive"))
      (node (ref "C5") (pin "1") (pinfunction "1_1") (pintype "passive"))
      (node (ref "C6") (pin "1") (pinfunction "1_1") (pintype "passive"))
      (node (ref "C7") (pin "1") (pinfunction "1_1") (pintype "passive"))
      (node (ref "C8") (pin "2") (pinfunction "2_2") (pintype "passive"))
      (node (ref "C9") (pin "2") (pinfunction "2_2") (pintype "passive"))
      (node (ref "D3") (pin "2") (pinfunction "K_2") (pintype "passive"))
      (node (ref "D4") (pin "2") (pinfunction "K_2") (pintype "passive"))
      (node (ref "IC3") (pin "1") (pinfunction "GND_1") (pintype "power_in"))
      (node (ref "IC3") (pin "16") (pinfunction "GND_4_16") (pintype "power_in"))
      (node (ref "IC3") (pin "17") (pinfunction "EP_17") (pintype "power_in"))
      (node (ref "IC3") (pin "7") (pinfunction "GND_1_7") (pintype "power_in"))
      (node (ref "IC3") (pin "8") (pinfunction "GND_2_8") (pintype "power_in"))
      (node (ref "IC3") (pin "9") (pinfunction "GND_3_9") (pintype "power_in"))
      (node (ref "IC5") (pin "3") (pinfunction "GND_3") (pintype "passive"))
      (node (ref "IC5") (pin "5") (pinfunction "VL_5") (pintype "passive"))
      (node (ref "IC5") (pin "7") (pinfunction "V-_7") (pintype "passive"))
      (node (ref "JP2") (pin "2") (pinfunction "2_2") (pintype "passive"))
      (node (ref "L1") (pin "2") (pinfunction "2_2") (pintype "passive"))
      (node (ref "R1") (pin "2") (pinfunction "2_2") (pintype "passive"))
      (node (ref "R16") (pin "1") (pinfunction "1_1") (pintype "passive"))
      (node (ref "R24") (pin "2") (pinfunction "2_2") (pintype "passive"))
      (node (ref "R25") (pin "1") (pinfunction "1_1") (pintype "passive"))
      (node (ref "R26") (pin "2") (pinfunction "2_2") (pintype "passive"))
      (node (ref "R27") (pin "1") (pinfunction "1_1") (pintype "passive"))
      (node (ref "R28") (pin "1") (pinfunction "1_1") (pintype "passive"))
      (node (ref "R36") (pin "1") (pinfunction "1_1") (pintype "passive"))
      (node (ref "R37") (pin "1") (pinfunction "1_1") (pintype "passive"))
      (node (ref "R38") (pin "1") (pinfunction "1_1") (pintype "passive"))
      (node (ref "R39") (pin "1") (pinfunction "1_1") (pintype "passive"))
      (node (ref "R41") (pin "1") (pinfunction "1_1") (pintype "passive"))
      (node (ref "R43") (pin "1") (pinfunction "1_1") (pintype "passive"))
      (node (ref "R45") (pin "1") (pinfunction "1_1") (pintype "passive"))
      (node (ref "R48") (pin "2") (pinfunction "2_2") (pintype "passive"))
      (node (ref "R49") (pin "2") (pinfunction "2_2") (pintype "passive"))
      (node (ref "R51") (pin "2") (pinfunction "2_2") (pintype "passive"))
      (node (ref "R9") (pin "1") (pinfunction "1_1") (pintype "passive"))
      (node (ref "SG1") (pin "1") (pinfunction "Y_1") (pintype "passive"))
      (node (ref "SG2") (pin "2") (pinfunction "X_2") (pintype "passive"))
      (node (ref "U1") (pin "4") (pinfunction "V-_4") (pintype "power_in"))
      (node (ref "U2") (pin "3") (pinfunction "GND_3") (pintype "power_in"))
      (node (ref "U3") (pin "0") (pinfunction "EPAD_0") (pintype "passive"))
      (node (ref "U3") (pin "10") (pinfunction "GND_10") (pintype "passive"))
      (node (ref "U3") (pin "11") (pinfunction "GND_11") (pintype "passive"))
      (node (ref "U3") (pin "14") (pinfunction "GND_14") (pintype "passive"))
      (node (ref "U3") (pin "18") (pinfunction "GND_18") (pintype "passive"))
      (node (ref "U3") (pin "2") (pinfunction "GND_2") (pintype "passive"))
      (node (ref "U3") (pin "4") (pinfunction "GND_4") (pintype "passive"))
      (node (ref "U3") (pin "7") (pinfunction "GND_7") (pintype "passive"))
    )
    (net (code "32") (name "Net-(C1-Pad1)") (class "Default")
      (node (ref "C1") (pin "1") (pinfunction "1_1") (pintype "passive"))
      (node (ref "FB1") (pin "1") (pinfunction "1_1") (pintype "passive"))
      (node (ref "R3") (pin "2") (pinfunction "2_2") (pintype "passive"))
    )
    (net (code "33") (name "Net-(C6-Pad2)") (class "Default")
      (node (ref "C6") (pin "2") (pinfunction "2_2") (pintype "passive"))
      (node (ref "R4") (pin "1") (pinfunction "1_1") (pintype "passive"))
      (node (ref "R6") (pin "2") (pinfunction "2_2") (pintype "passive"))
    )
    (net (code "34") (name "Net-(C7-Pad2)") (class "Default")
      (node (ref "C7") (pin "2") (pinfunction "2_2") (pintype "passive"))
      (node (ref "R4") (pin "2") (pinfunction "2_2") (pintype "passive"))
      (node (ref "R7") (pin "1") (pinfunction "1_1") (pintype "passive"))
    )
    (net (code "35") (name "Net-(C14-Pad1)") (class "Default")
      (node (ref "C14") (pin "1") (pinfunction "1_1") (pintype "passive"))
      (node (ref "FB5") (pin "2") (pinfunction "2_2") (pintype "passive"))
      (node (ref "R15") (pin "1") (pinfunction "1_1") (pintype "passive"))
    )
    (net (code "36") (name "Net-(C22-Pad1)") (class "Default")
      (node (ref "C22") (pin "1") (pinfunction "1_1") (pintype "passive"))
      (node (ref "FB7") (pin "1") (pinfunction "1_1") (pintype "passive"))
      (node (ref "U3") (pin "49") (pinfunction "OVDD_49") (pintype "passive"))
    )
    (net (code "37") (name "Net-(C28-Pad2)") (class "Default")
      (node (ref "C28") (pin "2") (pinfunction "2_2") (pintype "passive"))
      (node (ref "T1") (pin "4") (pinfunction "4_4") (pintype "passive"))
    )
    (net (code "38") (name "Net-(C29-Pad1)") (class "Default")
      (node (ref "C29") (pin "1") (pinfunction "1_1") (pintype "passive"))
      (node (ref "R31") (pin "1") (pinfunction "1_1") (pintype "passive"))
      (node (ref "R34") (pin "2") (pinfunction "2_2") (pintype "passive"))
      (node (ref "T1") (pin "1") (pinfunction "1_1") (pintype "passive"))
    )
    (net (code "39") (name "Net-(C29-Pad2)") (class "Default")
      (node (ref "C29") (pin "2") (pinfunction "2_2") (pintype "passive"))
      (node (ref "R32") (pin "1") (pinfunction "1_1") (pintype "passive"))
      (node (ref "R35") (pin "1") (pinfunction "1_1") (pintype "passive"))
      (node (ref "T1") (pin "3") (pinfunction "3_3") (pintype "passive"))
    )
    (net (code "40") (name "Net-(C30-Pad2)") (class "Default")
      (node (ref "C30") (pin "2") (pinfunction "2_2") (pintype "passive"))
      (node (ref "T1") (pin "5") (pinfunction "5_5") (pintype "passive"))
    )
    (net (code "41") (name "Net-(C31-Pad2)") (class "Default")
      (node (ref "C31") (pin "2") (pinfunction "2_2") (pintype "passive"))
      (node (ref "R32") (pin "2") (pinfunction "2_2") (pintype "passive"))
      (node (ref "R34") (pin "1") (pinfunction "1_1") (pintype "passive"))
      (node (ref "T1") (pin "2") (pinfunction "2_2") (pintype "passive"))
    )
    (net (code "42") (name "Net-(C32-Pad2)") (class "Default")
      (node (ref "C32") (pin "2") (pinfunction "2_2") (pintype "passive"))
      (node (ref "FB8") (pin "1") (pinfunction "1_1") (pintype "passive"))
      (node (ref "U3") (pin "32") (pinfunction "OVDD_32") (pintype "passive"))
    )
    (net (code "43") (name "Net-(D1-A)") (class "Default")
      (node (ref "C10") (pin "1") (pinfunction "1_1") (pintype "passive"))
      (node (ref "C13") (pin "1") (pinfunction "1_1") (pintype "passive"))
      (node (ref "C16") (pin "2") (pinfunction "2_2") (pintype "passive"))
      (node (ref "D1") (pin "1") (pinfunction "A_1") (pintype "passive"))
      (node (ref "FB9") (pin "1") (pinfunction "1_1") (pintype "passive"))
      (node (ref "IC4") (pin "4") (pinfunction "GND_4") (pintype "passive"))
      (node (ref "R44") (pin "2") (pinfunction "2_2") (pintype "passive"))
    )
    (net (code "44") (name "Net-(D1-K)") (class "Default")
      (node (ref "D1") (pin "2") (pinfunction "K_2") (pintype "passive"))
      (node (ref "IC4") (pin "2") (pinfunction "SE_2") (pintype "passive"))
      (node (ref "L1") (pin "1") (pinfunction "1_1") (pintype "passive"))
    )
    (net (code "45") (name "Net-(D2-A)") (class "Default")
      (node (ref "D2") (pin "1") (pinfunction "A_1") (pintype "passive"))
      (node (ref "JP2") (pin "1") (pinfunction "1_1") (pintype "passive"))
    )
    (net (code "46") (name "Net-(D2-K)") (class "Default")
      (node (ref "D2") (pin "2") (pinfunction "K_2") (pintype "passive"))
      (node (ref "L2") (pin "1") (pinfunction "1_1") (pintype "passive"))
    )
    (net (code "47") (name "Net-(D3-A)") (class "Default")
      (node (ref "D3") (pin "1") (pinfunction "A_1") (pintype "passive"))
      (node (ref "R50") (pin "1") (pinfunction "1_1") (pintype "passive"))
    )
    (net (code "48") (name "Net-(D4-A)") (class "Default")
      (node (ref "D4") (pin "1") (pinfunction "A_1") (pintype "passive"))
      (node (ref "R22") (pin "1") (pinfunction "1_1") (pintype "passive"))
    )
    (net (code "49") (name "Net-(D5-A)") (class "Default")
      (node (ref "D5") (pin "1") (pinfunction "A_1") (pintype "passive"))
      (node (ref "R51") (pin "1") (pinfunction "1_1") (pintype "passive"))
    )
    (net (code "50") (name "Net-(IC1A-IN+)") (class "Default")
      (node (ref "IC1") (pin "3") (pinfunction "IN+_3") (pintype "passive"))
      (node (ref "R14") (pin "1") (pinfunction "1_1") (pintype "passive"))
      (node (ref "R8") (pin "2") (pinfunction "2_2") (pintype "passive"))
      (node (ref "R9") (pin "2") (pinfunction "2_2") (pintype "passive"))
    )
    (net (code "51") (name "Net-(IC1A-IN-)") (class "Default")
      (node (ref "C2") (pin "1") (pinfunction "1_1") (pintype "passive"))
      (node (ref "IC1") (pin "2") (pinfunction "IN-_2") (pintype "passive"))
      (node (ref "R1") (pin "1") (pinfunction "1_1") (pintype "passive"))
      (node (ref "R2") (pin "1") (pinfunction "1_1") (pintype "passive"))
    )
    (net (code "52") (name "Net-(IC1A-OUT)") (class "Default")
      (node (ref "C2") (pin "2") (pinfunction "2_2") (pintype "passive"))
      (node (ref "IC1") (pin "6") (pinfunction "OUT_6") (pintype "passive"))
      (node (ref "R14") (pin "2") (pinfunction "2_2") (pintype "passive"))
      (node (ref "R2") (pin "2") (pinfunction "2_2") (pintype "passive"))
      (node (ref "R6") (pin "1") (pinfunction "1_1") (pintype "passive"))
    )
    (net (code "53") (name "Net-(IC1A-V+)") (class "Default")
      (node (ref "C4") (pin "1") (pinfunction "1_1") (pintype "passive"))
      (node (ref "FB3") (pin "1") (pinfunction "1_1") (pintype "passive"))
      (node (ref "IC1") (pin "7") (pinfunction "V+_7") (pintype "power_in"))
    )
    (net (code "54") (name "Net-(IC1A-V-)") (class "Default")
      (node (ref "C9") (pin "1") (pinfunction "1_1") (pintype "passive"))
      (node (ref "FB4") (pin "1") (pinfunction "1_1") (pintype "passive"))
      (node (ref "IC1") (pin "4") (pinfunction "V-_4") (pintype "power_in"))
    )
    (net (code "55") (name "Net-(IC2-+IN)") (class "Default")
      (node (ref "IC2") (pin "8") (pinfunction "+IN_8") (pintype "passive"))
      (node (ref "R5") (pin "1") (pinfunction "1_1") (pintype "passive"))
      (node (ref "R7") (pin "2") (pinfunction "2_2") (pintype "passive"))
    )
    (net (code "56") (name "Net-(IC2-+OUT)") (class "Default")
      (node (ref "IC2") (pin "4") (pinfunction "+OUT_4") (pintype "passive"))
      (node (ref "R13") (pin "1") (pinfunction "1_1") (pintype "passive"))
      (node (ref "R17") (pin "2") (pinfunction "2_2") (pintype "passive"))
    )
    (net (code "57") (name "Net-(IC2--IN)") (class "Default")
      (node (ref "IC2") (pin "1") (pinfunction "-IN_1") (pintype "passive"))
      (node (ref "R16") (pin "2") (pinfunction "2_2") (pintype "passive"))
      (node (ref "R17") (pin "1") (pinfunction "1_1") (pintype "passive"))
    )
    (net (code "58") (name "Net-(IC2--OUT)") (class "Default")
      (node (ref "IC2") (pin "5") (pinfunction "-OUT_5") (pintype "passive"))
      (node (ref "R10") (pin "1") (pinfunction "1_1") (pintype "passive"))
      (node (ref "R5") (pin "2") (pinfunction "2_2") (pintype "passive"))
    )
    (net (code "59") (name "Net-(IC2-V+)") (class "Default")
      (node (ref "C15") (pin "1") (pinfunction "1_1") (pintype "passive"))
      (node (ref "C34") (pin "1") (pinfunction "1_1") (pintype "passive"))
      (node (ref "FB6") (pin "1") (pinfunction "1_1") (pintype "passive"))
      (node (ref "IC2") (pin "3") (pinfunction "V+_3") (pintype "passive"))
    )
    (net (code "60") (name "Net-(IC2-V-)") (class "Default")
      (node (ref "C3") (pin "1") (pinfunction "1_1") (pintype "passive"))
      (node (ref "C33") (pin "1") (pinfunction "1_1") (pintype "passive"))
      (node (ref "FB2") (pin "1") (pinfunction "1_1") (pintype "passive"))
      (node (ref "IC2") (pin "6") (pinfunction "V-_6") (pintype "passive"))
    )
    (net (code "61") (name "Net-(IC3-ADJ)") (class "Default")
      (node (ref "IC3") (pin "6") (pinfunction "ADJ_6") (pintype "passive"))
      (node (ref "R23") (pin "1") (pinfunction "1_1") (pintype "passive"))
      (node (ref "R28") (pin "2") (pinfunction "2_2") (pintype "passive"))
    )
    (net (code "62") (name "Net-(IC4-DRI)") (class "Default")
      (node (ref "IC4") (pin "1") (pinfunction "SC_1") (pintype "passive"))
      (node (ref "IC4") (pin "7") (pinfunction "IPK_7") (pintype "passive"))
      (node (ref "IC4") (pin "8") (pinfunction "DRI_8") (pintype "passive"))
      (node (ref "R11") (pin "2") (pinfunction "2_2") (pintype "passive"))
    )
    (net (code "63") (name "Net-(IC4-FB)") (class "Default")
      (node (ref "IC4") (pin "5") (pinfunction "FB_5") (pintype "passive"))
      (node (ref "R44") (pin "1") (pinfunction "1_1") (pintype "passive"))
      (node (ref "R45") (pin "2") (pinfunction "2_2") (pintype "passive"))
    )
    (net (code "64") (name "Net-(IC4-TC)") (class "Default")
      (node (ref "C10") (pin "2") (pinfunction "2_2") (pintype "passive"))
      (node (ref "IC4") (pin "3") (pinfunction "TC_3") (pintype "passive"))
    )
    (net (code "65") (name "Net-(Q1-D)") (class "Default")
      (node (ref "Q1") (pin "3") (pinfunction "D_3") (pintype "passive"))
      (node (ref "R3") (pin "1") (pinfunction "1_1") (pintype "passive"))
    )
    (net (code "66") (name "Net-(Q1-G)") (class "Default")
      (node (ref "Q1") (pin "1") (pinfunction "G_1") (pintype "passive"))
      (node (ref "SG1") (pin "2") (pinfunction "X_2") (pintype "passive"))
    )
    (net (code "67") (name "Net-(Q1-S)") (class "Default")
      (node (ref "Q1") (pin "2") (pinfunction "S_2") (pintype "passive"))
      (node (ref "Q2") (pin "3") (pinfunction "D_3") (pintype "passive"))
      (node (ref "R8") (pin "1") (pinfunction "1_1") (pintype "passive"))
    )
    (net (code "68") (name "Net-(Q2-G)") (class "Default")
      (node (ref "Q2") (pin "1") (pinfunction "G_1") (pintype "passive"))
      (node (ref "R12") (pin "1") (pinfunction "1_1") (pintype "passive"))
      (node (ref "R15") (pin "2") (pinfunction "2_2") (pintype "passive"))
    )
    (net (code "69") (name "Net-(Q2-S)") (class "Default")
      (node (ref "Q2") (pin "2") (pinfunction "S_2") (pintype "passive"))
      (node (ref "R12") (pin "2") (pinfunction "2_2") (pintype "passive"))
    )
    (net (code "70") (name "Net-(SG2-Y)") (class "Default")
      (node (ref "C28") (pin "1") (pinfunction "1_1") (pintype "passive"))
      (node (ref "SG2") (pin "1") (pinfunction "Y_1") (pintype "passive"))
    )
    (net (code "71") (name "Net-(U1A-1IN+)") (class "Default")
      (node (ref "R46") (pin "1") (pinfunction "1_1") (pintype "passive"))
      (node (ref "U1") (pin "3") (pinfunction "1IN+_3") (pintype "input"))
    )
    (net (code "72") (name "Net-(U1B-2IN+)") (class "Default")
      (node (ref "R47") (pin "1") (pinfunction "1_1") (pintype "passive"))
      (node (ref "R48") (pin "1") (pinfunction "1_1") (pintype "passive"))
      (node (ref "U1") (pin "5") (pinfunction "2IN+_5") (pintype "input"))
    )
    (net (code "73") (name "Net-(U2-OUT)") (class "Default")
      (node (ref "C42") (pin "2") (pinfunction "2_2") (pintype "passive"))
      (node (ref "R47") (pin "2") (pinfunction "2_2") (pintype "passive"))
      (node (ref "U2") (pin "2") (pinfunction "OUT_2") (pintype "output"))
    )
    (net (code "74") (name "Net-(U3-DITH)") (class "Default")
      (node (ref "R42") (pin "1") (pinfunction "1_1") (pintype "passive"))
      (node (ref "R43") (pin "2") (pinfunction "2_2") (pintype "passive"))
      (node (ref "U3") (pin "20") (pinfunction "DITH_20") (pintype "passive"))
    )
    (net (code "75") (name "Net-(U3-LVDS)") (class "Default")
      (node (ref "R21") (pin "2") (pinfunction "2_2") (pintype "passive"))
      (node (ref "R27") (pin "2") (pinfunction "2_2") (pintype "passive"))
      (node (ref "U3") (pin "61") (pinfunction "LVDS_61") (pintype "passive"))
    )
    (net (code "76") (name "Net-(U3-MODE)") (class "Default")
      (node (ref "R20") (pin "2") (pinfunction "2_2") (pintype "passive"))
      (node (ref "R25") (pin "2") (pinfunction "2_2") (pintype "passive"))
      (node (ref "U3") (pin "62") (pinfunction "MODE_62") (pintype "passive"))
    )
    (net (code "77") (name "Net-(U3-RAND)") (class "Default")
      (node (ref "R19") (pin "2") (pinfunction "2_2") (pintype "passive"))
      (node (ref "R26") (pin "1") (pinfunction "1_1") (pintype "passive"))
      (node (ref "U3") (pin "63") (pinfunction "RAND_63") (pintype "passive"))
    )
    (net (code "78") (name "Net-(U3-SHDN)") (class "Default")
      (node (ref "R39") (pin "2") (pinfunction "2_2") (pintype "passive"))
      (node (ref "R40") (pin "1") (pinfunction "1_1") (pintype "passive"))
      (node (ref "U3") (pin "19") (pinfunction "SHDN_19") (pintype "passive"))
    )
    (net (code "79") (name "P-5V") (class "Default")
      (node (ref "C17") (pin "2") (pinfunction "2_2") (pintype "passive"))
      (node (ref "C5") (pin "2") (pinfunction "2_2") (pintype "passive"))
      (node (ref "D5") (pin "2") (pinfunction "K_2") (pintype "passive"))
      (node (ref "FB2") (pin "2") (pinfunction "2_2") (pintype "passive"))
      (node (ref "FB4") (pin "2") (pinfunction "2_2") (pintype "passive"))
      (node (ref "FB5") (pin "1") (pinfunction "1_1") (pintype "passive"))
      (node (ref "FB9") (pin "2") (pinfunction "2_2") (pintype "passive"))
    )
    (net (code "80") (name "P5V") (class "Default")
      (node (ref "C21") (pin "2") (pinfunction "2_2") (pintype "passive"))
      (node (ref "C35") (pin "1") (pinfunction "1_1") (pintype "passive"))
      (node (ref "C37") (pin "2") (pinfunction "2_2") (pintype "passive"))
      (node (ref "C38") (pin "2") (pinfunction "2_2") (pintype "passive"))
      (node (ref "FB1") (pin "2") (pinfunction "2_2") (pintype "passive"))
      (node (ref "FB10") (pin "2") (pinfunction "2_2") (pintype "passive"))
      (node (ref "FB3") (pin "2") (pinfunction "2_2") (pintype "passive"))
      (node (ref "FB6") (pin "2") (pinfunction "2_2") (pintype "passive"))
      (node (ref "IC3") (pin "10") (pinfunction "~{SHDN}_10") (pintype "passive"))
      (node (ref "IC3") (pin "12") (pinfunction "IN_12") (pintype "passive"))
      (node (ref "IC3") (pin "13") (pinfunction "IN_1_13") (pintype "passive"))
      (node (ref "IC3") (pin "14") (pinfunction "IN_2_14") (pintype "passive"))
      (node (ref "R50") (pin "2") (pinfunction "2_2") (pintype "passive"))
      (node (ref "U1") (pin "8") (pinfunction "V+_8") (pintype "power_in"))
    )
    (net (code "81") (name "P5V_Front") (class "Default")
      (node (ref "C11") (pin "1") (pinfunction "1_1") (pintype "passive"))
      (node (ref "C12") (pin "2") (pinfunction "2_2") (pintype "passive"))
      (node (ref "C36") (pin "2") (pinfunction "2_2") (pintype "passive"))
      (node (ref "FB10") (pin "1") (pinfunction "1_1") (pintype "passive"))
      (node (ref "IC4") (pin "6") (pinfunction "VCC_6") (pintype "passive"))
      (node (ref "JP3") (pin "2") (pinfunction "2_2") (pintype "passive"))
      (node (ref "R11") (pin "1") (pinfunction "1_1") (pintype "passive"))
    )
    (net (code "82") (name "P_EXT_5V") (class "Default")
      (node (ref "C18") (pin "1") (pinfunction "1_1") (pintype "passive"))
      (node (ref "JP3") (pin "1") (pinfunction "1_1") (pintype "passive"))
      (node (ref "L2") (pin "2") (pinfunction "2_2") (pintype "passive"))
    )
    (net (code "83") (name "P_FPGA_5V") (class "Default")
      (node (ref "JP3") (pin "3") (pinfunction "3_3") (pintype "passive"))
      (node (ref "JP4") (pin "2") (pinfunction "2_2") (pintype "passive"))
      (node (ref "JP4") (pin "4") (pinfunction "4_4") (pintype "passive"))
    )
    (net (code "84") (name "unconnected-(IC1B-NC-Pad5)") (class "Default")
      (node (ref "IC1") (pin "5") (pinfunction "NC_5") (pintype "passive+no_connect"))
    )
    (net (code "85") (name "unconnected-(IC1B-NULL_1-Pad1)") (class "Default")
      (node (ref "IC1") (pin "1") (pinfunction "NULL_1_1") (pintype "passive+no_connect"))
    )
    (net (code "86") (name "unconnected-(IC1B-NULL_2-Pad8)") (class "Default")
      (node (ref "IC1") (pin "8") (pinfunction "NULL_2_8") (pintype "passive+no_connect"))
    )
    (net (code "87") (name "unconnected-(IC2-NC-Pad7)") (class "Default")
      (node (ref "IC2") (pin "7") (pinfunction "NC_7") (pintype "passive+no_connect"))
    )
    (net (code "88") (name "unconnected-(IC3-NC-Pad2)") (class "Default")
      (node (ref "IC3") (pin "2") (pinfunction "NC_2") (pintype "passive+no_connect"))
    )
    (net (code "89") (name "unconnected-(IC3-NC_1-Pad11)") (class "Default")
      (node (ref "IC3") (pin "11") (pinfunction "NC_1_11") (pintype "passive+no_connect"))
    )
    (net (code "90") (name "unconnected-(IC3-NC_2-Pad15)") (class "Default")
      (node (ref "IC3") (pin "15") (pinfunction "NC_2_15") (pintype "passive+no_connect"))
    )
    (net (code "91") (name "unconnected-(JP4-Pad1)") (class "Default")
      (node (ref "JP4") (pin "1") (pinfunction "1_1") (pintype "passive+no_connect"))
    )
    (net (code "92") (name "unconnected-(JP4-Pad7)") (class "Default")
      (node (ref "JP4") (pin "7") (pinfunction "7_7") (pintype "passive+no_connect"))
    )
    (net (code "93") (name "unconnected-(JP4-Pad10)") (class "Default")
      (node (ref "JP4") (pin "10") (pinfunction "10_10") (pintype "passive+no_connect"))
    )
    (net (code "94") (name "unconnected-(JP4-Pad26)") (class "Default")
      (node (ref "JP4") (pin "26") (pinfunction "26_26") (pintype "passive+no_connect"))
    )
    (net (code "95") (name "unconnected-(JP4-Pad27)") (class "Default")
      (node (ref "JP4") (pin "27") (pinfunction "27_27") (pintype "passive+no_connect"))
    )
    (net (code "96") (name "unconnected-(JP4-Pad28)") (class "Default")
      (node (ref "JP4") (pin "28") (pinfunction "28_28") (pintype "passive+no_connect"))
    )
    (net (code "97") (name "unconnected-(JP4-Pad29)") (class "Default")
      (node (ref "JP4") (pin "29") (pinfunction "29_29") (pintype "passive+no_connect"))
    )
    (net (code "98") (name "unconnected-(JP4-Pad31)") (class "Default")
      (node (ref "JP4") (pin "31") (pinfunction "31_31") (pintype "passive+no_connect"))
    )
    (net (code "99") (name "unconnected-(JP4-Pad37)") (class "Default")
      (node (ref "JP4") (pin "37") (pinfunction "37_37") (pintype "passive"))
    )
    (net (code "100") (name "unconnected-(JP4-Pad40)") (class "Default")
      (node (ref "JP4") (pin "40") (pinfunction "40_40") (pintype "passive"))
    )
    (net (code "101") (name "unconnected-(U3-CLKOUTB-Pad40)") (class "Default")
      (node (ref "U3") (pin "40") (pinfunction "CLKOUTB_40") (pintype "passive+no_connect"))
    )
    (net (code "102") (name "unconnected-(U3-DB0-Pad21)") (class "Default")
      (node (ref "U3") (pin "21") (pinfunction "DB0_21") (pintype "passive+no_connect"))
    )
    (net (code "103") (name "unconnected-(U3-DB1-Pad22)") (class "Default")
      (node (ref "U3") (pin "22") (pinfunction "DB1_22") (pintype "passive+no_connect"))
    )
    (net (code "104") (name "unconnected-(U3-DB2-Pad23)") (class "Default")
      (node (ref "U3") (pin "23") (pinfunction "DB2_23") (pintype "passive+no_connect"))
    )
    (net (code "105") (name "unconnected-(U3-DB3-Pad24)") (class "Default")
      (node (ref "U3") (pin "24") (pinfunction "DB3_24") (pintype "passive+no_connect"))
    )
    (net (code "106") (name "unconnected-(U3-DB4-Pad25)") (class "Default")
      (node (ref "U3") (pin "25") (pinfunction "DB4_25") (pintype "passive+no_connect"))
    )
    (net (code "107") (name "unconnected-(U3-DB5-Pad26)") (class "Default")
      (node (ref "U3") (pin "26") (pinfunction "DB5_26") (pintype "passive+no_connect"))
    )
    (net (code "108") (name "unconnected-(U3-DB6-Pad27)") (class "Default")
      (node (ref "U3") (pin "27") (pinfunction "DB6_27") (pintype "passive+no_connect"))
    )
    (net (code "109") (name "unconnected-(U3-DB7-Pad28)") (class "Default")
      (node (ref "U3") (pin "28") (pinfunction "DB7_28") (pintype "passive+no_connect"))
    )
    (net (code "110") (name "unconnected-(U3-DB8-Pad29)") (class "Default")
      (node (ref "U3") (pin "29") (pinfunction "DB8_29") (pintype "passive+no_connect"))
    )
    (net (code "111") (name "unconnected-(U3-DB9-Pad30)") (class "Default")
      (node (ref "U3") (pin "30") (pinfunction "DB9_30") (pintype "passive+no_connect"))
    )
    (net (code "112") (name "unconnected-(U3-DB10-Pad33)") (class "Default")
      (node (ref "U3") (pin "33") (pinfunction "DB10_33") (pintype "passive+no_connect"))
    )
    (net (code "113") (name "unconnected-(U3-DB11-Pad34)") (class "Default")
      (node (ref "U3") (pin "34") (pinfunction "DB11_34") (pintype "passive+no_connect"))
    )
    (net (code "114") (name "unconnected-(U3-DB12-Pad35)") (class "Default")
      (node (ref "U3") (pin "35") (pinfunction "DB12_35") (pintype "passive+no_connect"))
    )
    (net (code "115") (name "unconnected-(U3-DB13-Pad36)") (class "Default")
      (node (ref "U3") (pin "36") (pinfunction "DB13_36") (pintype "passive+no_connect"))
    )
    (net (code "116") (name "unconnected-(U3-DB14-Pad37)") (class "Default")
      (node (ref "U3") (pin "37") (pinfunction "DB14_37") (pintype "passive+no_connect"))
    )
    (net (code "117") (name "unconnected-(U3-DB15-Pad38)") (class "Default")
      (node (ref "U3") (pin "38") (pinfunction "DB15_38") (pintype "passive+no_connect"))
    )
    (net (code "118") (name "unconnected-(U3-OFA-Pad60)") (class "Default")
      (node (ref "U3") (pin "60") (pinfunction "OFA_60") (pintype "passive+no_connect"))
    )
    (net (code "119") (name "unconnected-(U3-OFB-Pad39)") (class "Default")
      (node (ref "U3") (pin "39") (pinfunction "OFB_39") (pintype "passive+no_connect"))
    )
  )
)
